# bicore.net
KiCad netlist of a schematic drawn in EAGLE
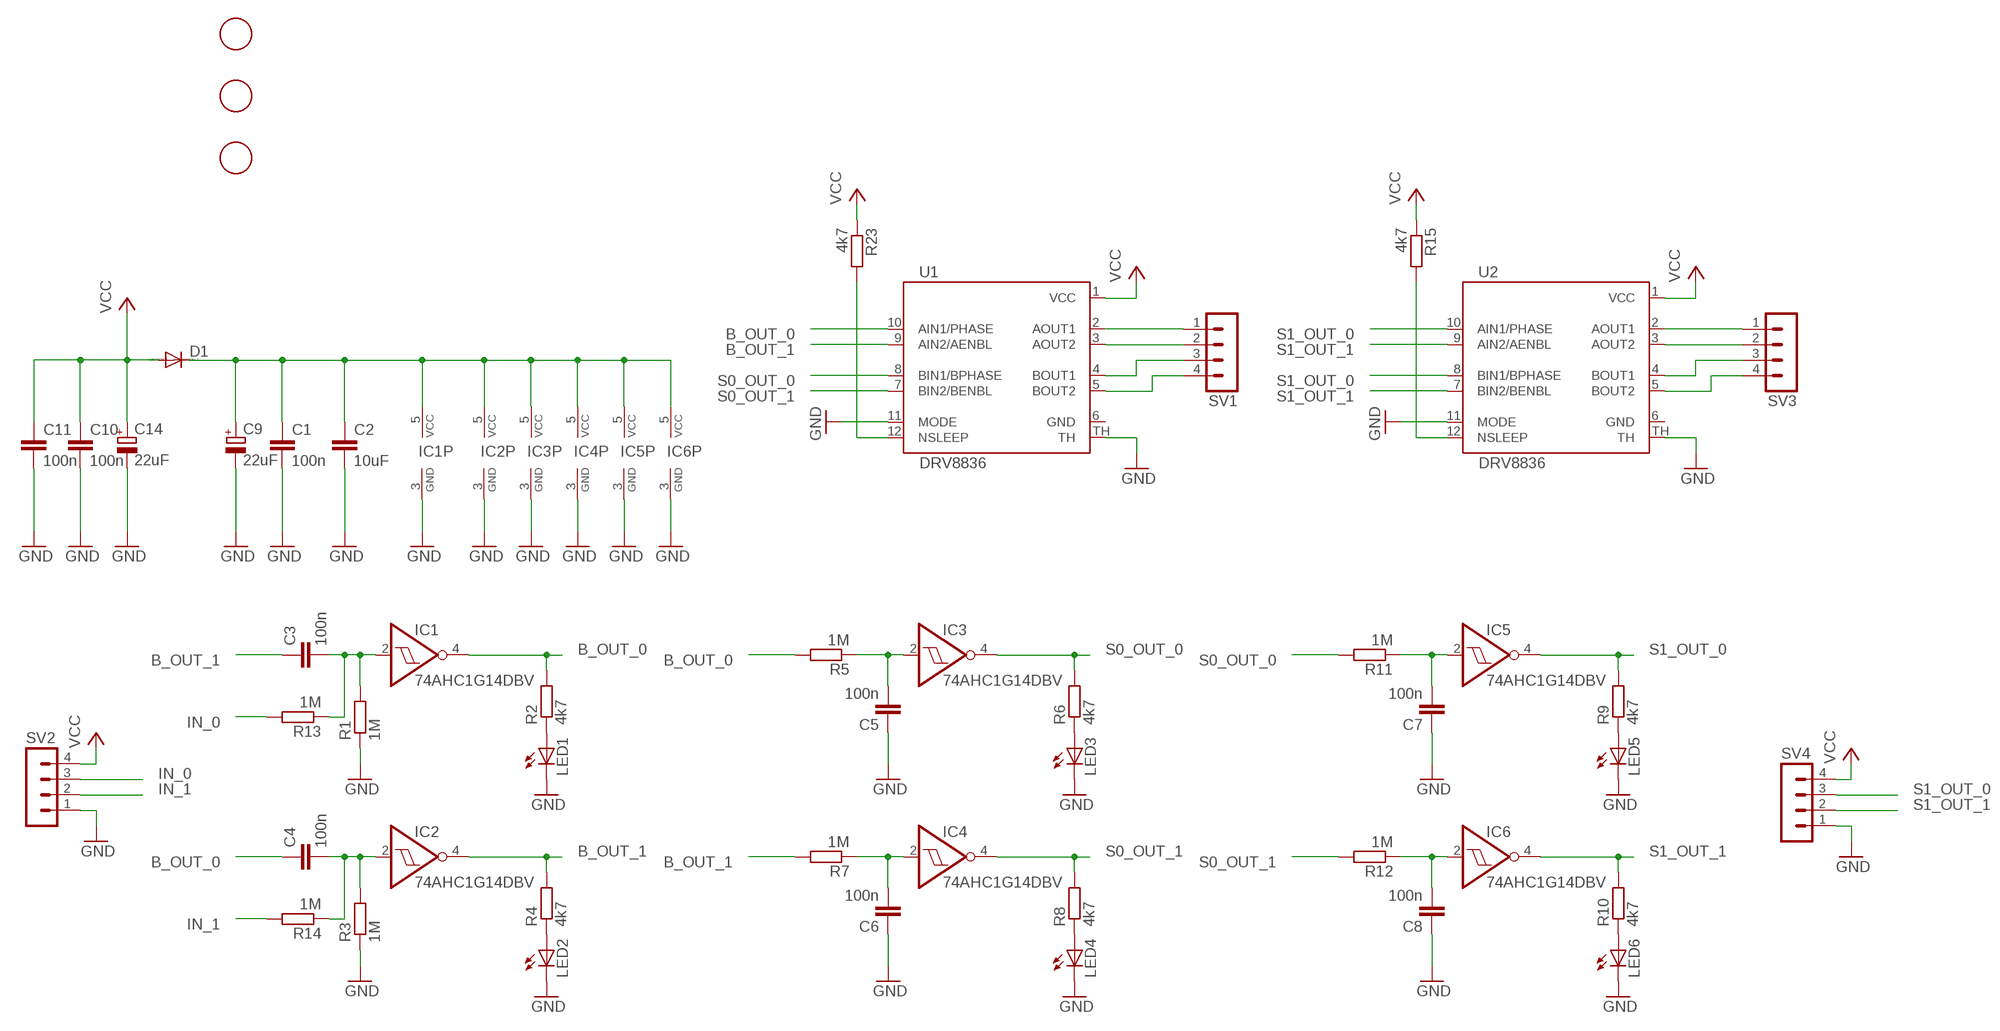
[diagram p0: schematic, sheet 1]

(export (version "E")
  (design (tool "Eeschema 10.0.6"))
  (components
    (comp (ref "C1")
      (value "100n")
      (footprint "eagle-import:C0805")
      (libsource (lib "eagle-import") (part "C-EUC0805"))
    )
    (comp (ref "C2")
      (value "10uF")
      (footprint "eagle-import:C0805")
      (libsource (lib "eagle-import") (part "C-EUC0805"))
    )
    (comp (ref "C3")
      (value "100n")
      (footprint "eagle-import:C0805")
      (libsource (lib "eagle-import") (part "C-EUC0805"))
    )
    (comp (ref "C4")
      (value "100n")
      (footprint "eagle-import:C0805")
      (libsource (lib "eagle-import") (part "C-EUC0805"))
    )
    (comp (ref "C5")
      (value "100n")
      (footprint "eagle-import:C0805")
      (libsource (lib "eagle-import") (part "C-EUC0805"))
    )
    (comp (ref "C6")
      (value "100n")
      (footprint "eagle-import:C0805")
      (libsource (lib "eagle-import") (part "C-EUC0805"))
    )
    (comp (ref "C7")
      (value "100n")
      (footprint "eagle-import:C0805")
      (libsource (lib "eagle-import") (part "C-EUC0805"))
    )
    (comp (ref "C8")
      (value "100n")
      (footprint "eagle-import:C0805")
      (libsource (lib "eagle-import") (part "C-EUC0805"))
    )
    (comp (ref "C9")
      (value "22uF")
      (footprint "eagle-import:153CLV-0605")
      (libsource (lib "eagle-import") (part "CPOL-EU153CLV-0605"))
    )
    (comp (ref "C10")
      (value "100n")
      (footprint "eagle-import:C0805")
      (libsource (lib "eagle-import") (part "C-EUC0805"))
    )
    (comp (ref "C11")
      (value "100n")
      (footprint "eagle-import:C0805")
      (libsource (lib "eagle-import") (part "C-EUC0805"))
    )
    (comp (ref "C14")
      (value "22uF")
      (footprint "eagle-import:153CLV-0605")
      (libsource (lib "eagle-import") (part "CPOL-EU153CLV-0605"))
    )
    (comp (ref "D1")
      (value "DIODE-DO214AA")
      (footprint "eagle-import:DO214AA")
      (libsource (lib "eagle-import") (part "DIODE-DO214AA"))
    )
    (comp (ref "IC1")
      (value "74AHC1G14DBV")
      (footprint "eagle-import:SOT23-5")
      (libsource (lib "eagle-import") (part "741G14DBVAHC"))
    )
    (comp (ref "IC2")
      (value "74AHC1G14DBV")
      (footprint "eagle-import:SOT23-5")
      (libsource (lib "eagle-import") (part "741G14DBVAHC"))
    )
    (comp (ref "IC3")
      (value "74AHC1G14DBV")
      (footprint "eagle-import:SOT23-5")
      (libsource (lib "eagle-import") (part "741G14DBVAHC"))
    )
    (comp (ref "IC4")
      (value "74AHC1G14DBV")
      (footprint "eagle-import:SOT23-5")
      (libsource (lib "eagle-import") (part "741G14DBVAHC"))
    )
    (comp (ref "IC5")
      (value "74AHC1G14DBV")
      (footprint "eagle-import:SOT23-5")
      (libsource (lib "eagle-import") (part "741G14DBVAHC"))
    )
    (comp (ref "IC6")
      (value "74AHC1G14DBV")
      (footprint "eagle-import:SOT23-5")
      (libsource (lib "eagle-import") (part "741G14DBVAHC"))
    )
    (comp (ref "LED1")
      (value "LEDSML1206")
      (footprint "eagle-import:SML1206")
      (libsource (lib "eagle-import") (part "LEDSML1206"))
    )
    (comp (ref "LED2")
      (value "LEDSML1206")
      (footprint "eagle-import:SML1206")
      (libsource (lib "eagle-import") (part "LEDSML1206"))
    )
    (comp (ref "LED3")
      (value "LEDSML1206")
      (footprint "eagle-import:SML1206")
      (libsource (lib "eagle-import") (part "LEDSML1206"))
    )
    (comp (ref "LED4")
      (value "LEDSML1206")
      (footprint "eagle-import:SML1206")
      (libsource (lib "eagle-import") (part "LEDSML1206"))
    )
    (comp (ref "LED5")
      (value "LEDSML1206")
      (footprint "eagle-import:SML1206")
      (libsource (lib "eagle-import") (part "LEDSML1206"))
    )
    (comp (ref "LED6")
      (value "LEDSML1206")
      (footprint "eagle-import:SML1206")
      (libsource (lib "eagle-import") (part "LEDSML1206"))
    )
    (comp (ref "R1")
      (value "1M")
      (footprint "eagle-import:M0805")
      (libsource (lib "eagle-import") (part "R-EU_M0805"))
    )
    (comp (ref "R2")
      (value "4k7")
      (footprint "eagle-import:M0805")
      (libsource (lib "eagle-import") (part "R-EU_M0805"))
    )
    (comp (ref "R3")
      (value "1M")
      (footprint "eagle-import:M0805")
      (libsource (lib "eagle-import") (part "R-EU_M0805"))
    )
    (comp (ref "R4")
      (value "4k7")
      (footprint "eagle-import:M0805")
      (libsource (lib "eagle-import") (part "R-EU_M0805"))
    )
    (comp (ref "R5")
      (value "1M")
      (footprint "eagle-import:M0805")
      (libsource (lib "eagle-import") (part "R-EU_M0805"))
    )
    (comp (ref "R6")
      (value "4k7")
      (footprint "eagle-import:M0805")
      (libsource (lib "eagle-import") (part "R-EU_M0805"))
    )
    (comp (ref "R7")
      (value "1M")
      (footprint "eagle-import:M0805")
      (libsource (lib "eagle-import") (part "R-EU_M0805"))
    )
    (comp (ref "R8")
      (value "4k7")
      (footprint "eagle-import:M0805")
      (libsource (lib "eagle-import") (part "R-EU_M0805"))
    )
    (comp (ref "R9")
      (value "4k7")
      (footprint "eagle-import:M0805")
      (libsource (lib "eagle-import") (part "R-EU_M0805"))
    )
    (comp (ref "R10")
      (value "4k7")
      (footprint "eagle-import:M0805")
      (libsource (lib "eagle-import") (part "R-EU_M0805"))
    )
    (comp (ref "R11")
      (value "1M")
      (footprint "eagle-import:M0805")
      (libsource (lib "eagle-import") (part "R-EU_M0805"))
    )
    (comp (ref "R12")
      (value "1M")
      (footprint "eagle-import:M0805")
      (libsource (lib "eagle-import") (part "R-EU_M0805"))
    )
    (comp (ref "R13")
      (value "1M")
      (footprint "eagle-import:M0805")
      (libsource (lib "eagle-import") (part "R-EU_M0805"))
    )
    (comp (ref "R14")
      (value "1M")
      (footprint "eagle-import:M0805")
      (libsource (lib "eagle-import") (part "R-EU_M0805"))
    )
    (comp (ref "R15")
      (value "4k7")
      (footprint "eagle-import:M0805")
      (libsource (lib "eagle-import") (part "R-EU_M0805"))
    )
    (comp (ref "R23")
      (value "4k7")
      (footprint "eagle-import:M0805")
      (libsource (lib "eagle-import") (part "R-EU_M0805"))
    )
    (comp (ref "SV1")
      (value "MA04-1")
      (footprint "eagle-import:MA04-1")
      (libsource (lib "eagle-import") (part "MA04-1"))
    )
    (comp (ref "SV2")
      (value "MA04-1")
      (footprint "eagle-import:MA04-1")
      (libsource (lib "eagle-import") (part "MA04-1"))
    )
    (comp (ref "SV3")
      (value "MA04-1")
      (footprint "eagle-import:MA04-1")
      (libsource (lib "eagle-import") (part "MA04-1"))
    )
    (comp (ref "SV4")
      (value "MA04-1")
      (footprint "eagle-import:MA04-1")
      (libsource (lib "eagle-import") (part "MA04-1"))
    )
    (comp (ref "U$1")
      (value "ADAFRUIT_FIDUCIAL")
      (footprint "eagle-import:ADAFRUIT_FIDUCIAL_1MM")
      (libsource (lib "eagle-import") (part "ADAFRUIT_FIDUCIAL"))
    )
    (comp (ref "U$2")
      (value "ADAFRUIT_FIDUCIAL")
      (footprint "eagle-import:ADAFRUIT_FIDUCIAL_1MM")
      (libsource (lib "eagle-import") (part "ADAFRUIT_FIDUCIAL"))
    )
    (comp (ref "U$3")
      (value "ADAFRUIT_FIDUCIAL")
      (footprint "eagle-import:ADAFRUIT_FIDUCIAL_1MM")
      (libsource (lib "eagle-import") (part "ADAFRUIT_FIDUCIAL"))
    )
    (comp (ref "U1")
      (value "DRV8836")
      (footprint "eagle-import:12WSON")
      (libsource (lib "eagle-import") (part "DRV8836"))
    )
    (comp (ref "U2")
      (value "DRV8836")
      (footprint "eagle-import:12WSON")
      (libsource (lib "eagle-import") (part "DRV8836"))
    )
  )
  (nets
    (net (code "1") (name "/B_OUT_0") (class "Default")
      (node (ref "C4") (pin "1") (pinfunction "1_1") (pintype "passive"))
      (node (ref "IC1") (pin "4") (pinfunction "O_4") (pintype "output"))
      (node (ref "R2") (pin "2") (pinfunction "2_2") (pintype "passive"))
      (node (ref "R5") (pin "2") (pinfunction "2_2") (pintype "passive"))
      (node (ref "U1") (pin "10") (pinfunction "AIN1/PHASE_10") (pintype "bidirectional"))
    )
    (net (code "2") (name "/B_OUT_1") (class "Default")
      (node (ref "C3") (pin "1") (pinfunction "1_1") (pintype "passive"))
      (node (ref "IC2") (pin "4") (pinfunction "O_4") (pintype "output"))
      (node (ref "R4") (pin "2") (pinfunction "2_2") (pintype "passive"))
      (node (ref "R7") (pin "2") (pinfunction "2_2") (pintype "passive"))
      (node (ref "U1") (pin "9") (pinfunction "AIN2/AENBL_9") (pintype "bidirectional"))
    )
    (net (code "3") (name "/IN_0") (class "Default")
      (node (ref "R13") (pin "2") (pinfunction "2_2") (pintype "passive"))
      (node (ref "SV2") (pin "3") (pinfunction "3_3") (pintype "passive"))
    )
    (net (code "4") (name "/IN_1") (class "Default")
      (node (ref "R14") (pin "2") (pinfunction "2_2") (pintype "passive"))
      (node (ref "SV2") (pin "2") (pinfunction "2_2") (pintype "passive"))
    )
    (net (code "5") (name "/S0_OUT_0") (class "Default")
      (node (ref "IC3") (pin "4") (pinfunction "O_4") (pintype "output"))
      (node (ref "R11") (pin "2") (pinfunction "2_2") (pintype "passive"))
      (node (ref "R6") (pin "2") (pinfunction "2_2") (pintype "passive"))
      (node (ref "U1") (pin "8") (pinfunction "BIN1/BPHASE_8") (pintype "bidirectional"))
    )
    (net (code "6") (name "/S0_OUT_1") (class "Default")
      (node (ref "IC4") (pin "4") (pinfunction "O_4") (pintype "output"))
      (node (ref "R12") (pin "2") (pinfunction "2_2") (pintype "passive"))
      (node (ref "R8") (pin "2") (pinfunction "2_2") (pintype "passive"))
      (node (ref "U1") (pin "7") (pinfunction "BIN2/BENBL_7") (pintype "bidirectional"))
    )
    (net (code "7") (name "/S1_OUT_0") (class "Default")
      (node (ref "IC5") (pin "4") (pinfunction "O_4") (pintype "output"))
      (node (ref "R9") (pin "2") (pinfunction "2_2") (pintype "passive"))
      (node (ref "SV4") (pin "3") (pinfunction "3_3") (pintype "passive"))
      (node (ref "U2") (pin "10") (pinfunction "AIN1/PHASE_10") (pintype "bidirectional"))
      (node (ref "U2") (pin "8") (pinfunction "BIN1/BPHASE_8") (pintype "bidirectional"))
    )
    (net (code "8") (name "/S1_OUT_1") (class "Default")
      (node (ref "IC6") (pin "4") (pinfunction "O_4") (pintype "output"))
      (node (ref "R10") (pin "2") (pinfunction "2_2") (pintype "passive"))
      (node (ref "SV4") (pin "2") (pinfunction "2_2") (pintype "passive"))
      (node (ref "U2") (pin "7") (pinfunction "BIN2/BENBL_7") (pintype "bidirectional"))
      (node (ref "U2") (pin "9") (pinfunction "AIN2/AENBL_9") (pintype "bidirectional"))
    )
    (net (code "9") (name "GND") (class "Default")
      (node (ref "C1") (pin "2") (pinfunction "2_2") (pintype "passive"))
      (node (ref "C10") (pin "2") (pinfunction "2_2") (pintype "passive"))
      (node (ref "C11") (pin "2") (pinfunction "2_2") (pintype "passive"))
      (node (ref "C14") (pin "-") (pinfunction "-_-") (pintype "passive"))
      (node (ref "C2") (pin "2") (pinfunction "2_2") (pintype "passive"))
      (node (ref "C5") (pin "1") (pinfunction "1_1") (pintype "passive"))
      (node (ref "C6") (pin "1") (pinfunction "1_1") (pintype "passive"))
      (node (ref "C7") (pin "1") (pinfunction "1_1") (pintype "passive"))
      (node (ref "C8") (pin "1") (pinfunction "1_1") (pintype "passive"))
      (node (ref "C9") (pin "-") (pinfunction "-_-") (pintype "passive"))
      (node (ref "IC1") (pin "3") (pinfunction "GND_3") (pintype "power_in"))
      (node (ref "IC2") (pin "3") (pinfunction "GND_3") (pintype "power_in"))
      (node (ref "IC3") (pin "3") (pinfunction "GND_3") (pintype "power_in"))
      (node (ref "IC4") (pin "3") (pinfunction "GND_3") (pintype "power_in"))
      (node (ref "IC5") (pin "3") (pinfunction "GND_3") (pintype "power_in"))
      (node (ref "IC6") (pin "3") (pinfunction "GND_3") (pintype "power_in"))
      (node (ref "LED1") (pin "C") (pinfunction "C_C") (pintype "passive"))
      (node (ref "LED2") (pin "C") (pinfunction "C_C") (pintype "passive"))
      (node (ref "LED3") (pin "C") (pinfunction "C_C") (pintype "passive"))
      (node (ref "LED4") (pin "C") (pinfunction "C_C") (pintype "passive"))
      (node (ref "LED5") (pin "C") (pinfunction "C_C") (pintype "passive"))
      (node (ref "LED6") (pin "C") (pinfunction "C_C") (pintype "passive"))
      (node (ref "R1") (pin "1") (pinfunction "1_1") (pintype "passive"))
      (node (ref "R3") (pin "1") (pinfunction "1_1") (pintype "passive"))
      (node (ref "SV2") (pin "1") (pinfunction "1_1") (pintype "passive"))
      (node (ref "SV4") (pin "1") (pinfunction "1_1") (pintype "passive"))
      (node (ref "U1") (pin "11") (pinfunction "MODE_11") (pintype "bidirectional"))
      (node (ref "U1") (pin "TH") (pinfunction "TH_TH") (pintype "bidirectional"))
      (node (ref "U2") (pin "11") (pinfunction "MODE_11") (pintype "bidirectional"))
      (node (ref "U2") (pin "TH") (pinfunction "TH_TH") (pintype "bidirectional"))
    )
    (net (code "10") (name "Net-(IC1A-I)") (class "Default")
      (node (ref "C3") (pin "2") (pinfunction "2_2") (pintype "passive"))
      (node (ref "IC1") (pin "2") (pinfunction "I_2") (pintype "input"))
      (node (ref "R1") (pin "2") (pinfunction "2_2") (pintype "passive"))
      (node (ref "R13") (pin "1") (pinfunction "1_1") (pintype "passive"))
    )
    (net (code "11") (name "Net-(IC1B-VCC)") (class "Default")
      (node (ref "C1") (pin "1") (pinfunction "1_1") (pintype "passive"))
      (node (ref "C2") (pin "1") (pinfunction "1_1") (pintype "passive"))
      (node (ref "C9") (pin "+") (pinfunction "+_+") (pintype "passive"))
      (node (ref "D1") (pin "C") (pinfunction "C_C") (pintype "passive"))
      (node (ref "IC1") (pin "5") (pinfunction "VCC_5") (pintype "power_in"))
      (node (ref "IC2") (pin "5") (pinfunction "VCC_5") (pintype "power_in"))
      (node (ref "IC3") (pin "5") (pinfunction "VCC_5") (pintype "power_in"))
      (node (ref "IC4") (pin "5") (pinfunction "VCC_5") (pintype "power_in"))
      (node (ref "IC5") (pin "5") (pinfunction "VCC_5") (pintype "power_in"))
      (node (ref "IC6") (pin "5") (pinfunction "VCC_5") (pintype "power_in"))
    )
    (net (code "12") (name "Net-(IC2A-I)") (class "Default")
      (node (ref "C4") (pin "2") (pinfunction "2_2") (pintype "passive"))
      (node (ref "IC2") (pin "2") (pinfunction "I_2") (pintype "input"))
      (node (ref "R14") (pin "1") (pinfunction "1_1") (pintype "passive"))
      (node (ref "R3") (pin "2") (pinfunction "2_2") (pintype "passive"))
    )
    (net (code "13") (name "Net-(IC3A-I)") (class "Default")
      (node (ref "C5") (pin "2") (pinfunction "2_2") (pintype "passive"))
      (node (ref "IC3") (pin "2") (pinfunction "I_2") (pintype "input"))
      (node (ref "R5") (pin "1") (pinfunction "1_1") (pintype "passive"))
    )
    (net (code "14") (name "Net-(IC4A-I)") (class "Default")
      (node (ref "C6") (pin "2") (pinfunction "2_2") (pintype "passive"))
      (node (ref "IC4") (pin "2") (pinfunction "I_2") (pintype "input"))
      (node (ref "R7") (pin "1") (pinfunction "1_1") (pintype "passive"))
    )
    (net (code "15") (name "Net-(IC5A-I)") (class "Default")
      (node (ref "C7") (pin "2") (pinfunction "2_2") (pintype "passive"))
      (node (ref "IC5") (pin "2") (pinfunction "I_2") (pintype "input"))
      (node (ref "R11") (pin "1") (pinfunction "1_1") (pintype "passive"))
    )
    (net (code "16") (name "Net-(IC6A-I)") (class "Default")
      (node (ref "C8") (pin "2") (pinfunction "2_2") (pintype "passive"))
      (node (ref "IC6") (pin "2") (pinfunction "I_2") (pintype "input"))
      (node (ref "R12") (pin "1") (pinfunction "1_1") (pintype "passive"))
    )
    (net (code "17") (name "Net-(LED1-PadA)") (class "Default")
      (node (ref "LED1") (pin "A") (pinfunction "A_A") (pintype "passive"))
      (node (ref "R2") (pin "1") (pinfunction "1_1") (pintype "passive"))
    )
    (net (code "18") (name "Net-(LED2-PadA)") (class "Default")
      (node (ref "LED2") (pin "A") (pinfunction "A_A") (pintype "passive"))
      (node (ref "R4") (pin "1") (pinfunction "1_1") (pintype "passive"))
    )
    (net (code "19") (name "Net-(LED3-PadA)") (class "Default")
      (node (ref "LED3") (pin "A") (pinfunction "A_A") (pintype "passive"))
      (node (ref "R6") (pin "1") (pinfunction "1_1") (pintype "passive"))
    )
    (net (code "20") (name "Net-(LED4-PadA)") (class "Default")
      (node (ref "LED4") (pin "A") (pinfunction "A_A") (pintype "passive"))
      (node (ref "R8") (pin "1") (pinfunction "1_1") (pintype "passive"))
    )
    (net (code "21") (name "Net-(LED5-PadA)") (class "Default")
      (node (ref "LED5") (pin "A") (pinfunction "A_A") (pintype "passive"))
      (node (ref "R9") (pin "1") (pinfunction "1_1") (pintype "passive"))
    )
    (net (code "22") (name "Net-(LED6-PadA)") (class "Default")
      (node (ref "LED6") (pin "A") (pinfunction "A_A") (pintype "passive"))
      (node (ref "R10") (pin "1") (pinfunction "1_1") (pintype "passive"))
    )
    (net (code "23") (name "Net-(U1-AOUT1)") (class "Default")
      (node (ref "SV1") (pin "1") (pinfunction "1_1") (pintype "passive"))
      (node (ref "U1") (pin "2") (pinfunction "AOUT1_2") (pintype "bidirectional"))
    )
    (net (code "24") (name "Net-(U1-AOUT2)") (class "Default")
      (node (ref "SV1") (pin "2") (pinfunction "2_2") (pintype "passive"))
      (node (ref "U1") (pin "3") (pinfunction "AOUT2_3") (pintype "bidirectional"))
    )
    (net (code "25") (name "Net-(U1-BOUT1)") (class "Default")
      (node (ref "SV1") (pin "3") (pinfunction "3_3") (pintype "passive"))
      (node (ref "U1") (pin "4") (pinfunction "BOUT1_4") (pintype "bidirectional"))
    )
    (net (code "26") (name "Net-(U1-BOUT2)") (class "Default")
      (node (ref "SV1") (pin "4") (pinfunction "4_4") (pintype "passive"))
      (node (ref "U1") (pin "5") (pinfunction "BOUT2_5") (pintype "bidirectional"))
    )
    (net (code "27") (name "Net-(U1-NSLEEP)") (class "Default")
      (node (ref "R23") (pin "2") (pinfunction "2_2") (pintype "passive"))
      (node (ref "U1") (pin "12") (pinfunction "NSLEEP_12") (pintype "bidirectional"))
    )
    (net (code "28") (name "Net-(U2-AOUT1)") (class "Default")
      (node (ref "SV3") (pin "1") (pinfunction "1_1") (pintype "passive"))
      (node (ref "U2") (pin "2") (pinfunction "AOUT1_2") (pintype "bidirectional"))
    )
    (net (code "29") (name "Net-(U2-AOUT2)") (class "Default")
      (node (ref "SV3") (pin "2") (pinfunction "2_2") (pintype "passive"))
      (node (ref "U2") (pin "3") (pinfunction "AOUT2_3") (pintype "bidirectional"))
    )
    (net (code "30") (name "Net-(U2-BOUT1)") (class "Default")
      (node (ref "SV3") (pin "3") (pinfunction "3_3") (pintype "passive"))
      (node (ref "U2") (pin "4") (pinfunction "BOUT1_4") (pintype "bidirectional"))
    )
    (net (code "31") (name "Net-(U2-BOUT2)") (class "Default")
      (node (ref "SV3") (pin "4") (pinfunction "4_4") (pintype "passive"))
      (node (ref "U2") (pin "5") (pinfunction "BOUT2_5") (pintype "bidirectional"))
    )
    (net (code "32") (name "Net-(U2-NSLEEP)") (class "Default")
      (node (ref "R15") (pin "2") (pinfunction "2_2") (pintype "passive"))
      (node (ref "U2") (pin "12") (pinfunction "NSLEEP_12") (pintype "bidirectional"))
    )
    (net (code "33") (name "VCC") (class "Default")
      (node (ref "C10") (pin "1") (pinfunction "1_1") (pintype "passive"))
      (node (ref "C11") (pin "1") (pinfunction "1_1") (pintype "passive"))
      (node (ref "C14") (pin "+") (pinfunction "+_+") (pintype "passive"))
      (node (ref "D1") (pin "A") (pinfunction "A_A") (pintype "passive"))
      (node (ref "R15") (pin "1") (pinfunction "1_1") (pintype "passive"))
      (node (ref "R23") (pin "1") (pinfunction "1_1") (pintype "passive"))
      (node (ref "SV2") (pin "4") (pinfunction "4_4") (pintype "passive"))
      (node (ref "SV4") (pin "4") (pinfunction "4_4") (pintype "passive"))
      (node (ref "U1") (pin "1") (pinfunction "VCC_1") (pintype "bidirectional"))
      (node (ref "U2") (pin "1") (pinfunction "VCC_1") (pintype "bidirectional"))
    )
    (net (code "34") (name "unconnected-(U1-GND-Pad6)") (class "Default")
      (node (ref "U1") (pin "6") (pinfunction "GND_6") (pintype "bidirectional"))
    )
    (net (code "35") (name "unconnected-(U2-GND-Pad6)") (class "Default")
      (node (ref "U2") (pin "6") (pinfunction "GND_6") (pintype "bidirectional"))
    )
  )
)
